# micro_mousev1_0.net
KiCad netlist of a schematic drawn in Altium Designer
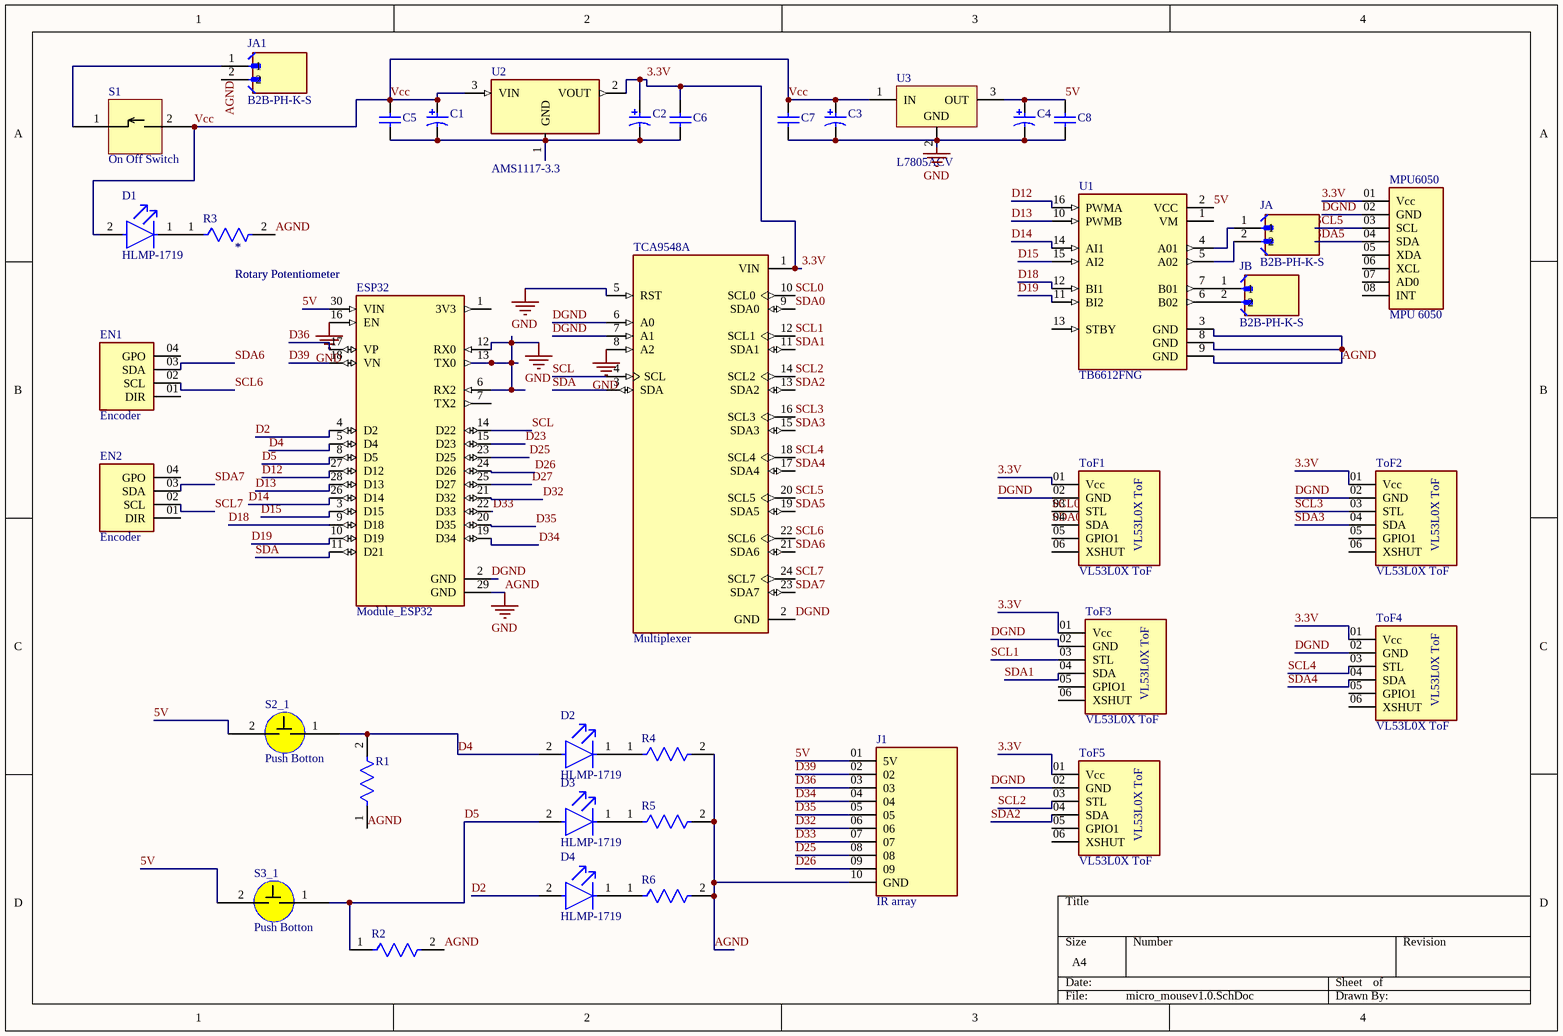
[diagram p0: micro_mousev1.0.SchDoc]

(export (version "E")
  (design (tool "Eeschema 10.0.6"))
  (components
    (comp (ref "C1")
      (value "ECA1HM100")
      (footprint "CAPPR55-200-1100X500X1200")
      (description "Aluminum Electrolytic Capacitor, 10 uF, +/- 20%, 50 V, -40 to 85 degC, 2-Pin THD, RoHS, Bulk")
      (fields (field (name "MANUFACTURER") "Panasonic") (field (name "TOLERANCE") "20%"))
      (libsource (lib "Altium Content Vault") (part "CAP-P-2"))
    )
    (comp (ref "C2")
      (value "ECA1HM100")
      (footprint "CAPPR55-200-1100X500X1200")
      (description "Aluminum Electrolytic Capacitor, 10 uF, +/- 20%, 50 V, -40 to 85 degC, 2-Pin THD, RoHS, Bulk")
      (fields (field (name "MANUFACTURER") "Panasonic") (field (name "TOLERANCE") "20%"))
      (libsource (lib "Altium Content Vault") (part "CAP-P-2"))
    )
    (comp (ref "C3")
      (value "ECA1HM100")
      (footprint "CAPPR55-200-1100X500X1200")
      (description "Aluminum Electrolytic Capacitor, 10 uF, +/- 20%, 50 V, -40 to 85 degC, 2-Pin THD, RoHS, Bulk")
      (fields (field (name "MANUFACTURER") "Panasonic") (field (name "TOLERANCE") "20%"))
      (libsource (lib "Altium Content Vault") (part "CAP-P-2"))
    )
    (comp (ref "C4")
      (value "ECA1HM100")
      (footprint "CAPPR55-200-1100X500X1200")
      (description "Aluminum Electrolytic Capacitor, 10 uF, +/- 20%, 50 V, -40 to 85 degC, 2-Pin THD, RoHS, Bulk")
      (fields (field (name "MANUFACTURER") "Panasonic") (field (name "TOLERANCE") "20%"))
      (libsource (lib "Altium Content Vault") (part "CAP-P-2"))
    )
    (comp (ref "C5")
      (value "K104K15X7RF5TL2")
      (footprint "VISH-K104K15X7RF5TL2")
      (description "Ceramic Capacitor, 100 nF, +/- 10%, 50 V, -55 to 125 degC, 2-Pin THD, RoHS, Tape and Reel")
      (fields (field (name "MANUFACTURER") "Vishay") (field (name "TOLERANCE") "±10%"))
      (libsource (lib "Altium Content Vault") (part "CAP-NP-2"))
    )
    (comp (ref "C6")
      (value "K104K15X7RF5TL2")
      (footprint "VISH-K104K15X7RF5TL2")
      (description "Ceramic Capacitor, 100 nF, +/- 10%, 50 V, -55 to 125 degC, 2-Pin THD, RoHS, Tape and Reel")
      (fields (field (name "MANUFACTURER") "Vishay") (field (name "TOLERANCE") "±10%"))
      (libsource (lib "Altium Content Vault") (part "CAP-NP-2"))
    )
    (comp (ref "C7")
      (value "K104K15X7RF5TL2")
      (footprint "VISH-K104K15X7RF5TL2")
      (description "Ceramic Capacitor, 100 nF, +/- 10%, 50 V, -55 to 125 degC, 2-Pin THD, RoHS, Tape and Reel")
      (fields (field (name "MANUFACTURER") "Vishay") (field (name "TOLERANCE") "±10%"))
      (libsource (lib "Altium Content Vault") (part "CAP-NP-2"))
    )
    (comp (ref "C8")
      (value "K104K15X7RF5TL2")
      (footprint "VISH-K104K15X7RF5TL2")
      (description "Ceramic Capacitor, 100 nF, +/- 10%, 50 V, -55 to 125 degC, 2-Pin THD, RoHS, Tape and Reel")
      (fields (field (name "MANUFACTURER") "Vishay") (field (name "TOLERANCE") "±10%"))
      (libsource (lib "Altium Content Vault") (part "CAP-NP-2"))
    )
    (comp (ref "D1")
      (value "HLMP-1719")
      (footprint "FP-HLMP-1719-MFG")
      (description "LED YELLOW DIFFUSED T-1 T/H")
      (fields
        (field (name "MANUFACTURER") "Broadcom")
        (field (name "OCTOPART") "https://octopart.com/hlmp-1719-broadcom-71130405")
      )
      (libsource (lib "Altium Content Vault") (part "8706943c75ba83719d021d2fdc84c58"))
    )
    (comp (ref "D2")
      (value "HLMP-1719")
      (footprint "FP-HLMP-1719-MFG")
      (description "LED YELLOW DIFFUSED T-1 T/H")
      (fields
        (field (name "MANUFACTURER") "Broadcom")
        (field (name "OCTOPART") "https://octopart.com/hlmp-1719-broadcom-71130405")
      )
      (libsource (lib "Altium Content Vault") (part "8706943c75ba83719d021d2fdc84c58"))
    )
    (comp (ref "D3")
      (value "HLMP-1719")
      (footprint "FP-HLMP-1719-MFG")
      (description "LED YELLOW DIFFUSED T-1 T/H")
      (fields
        (field (name "MANUFACTURER") "Broadcom")
        (field (name "OCTOPART") "https://octopart.com/hlmp-1719-broadcom-71130405")
      )
      (libsource (lib "Altium Content Vault") (part "8706943c75ba83719d021d2fdc84c58"))
    )
    (comp (ref "D4")
      (value "HLMP-1719")
      (footprint "FP-HLMP-1719-MFG")
      (description "LED YELLOW DIFFUSED T-1 T/H")
      (fields
        (field (name "MANUFACTURER") "Broadcom")
        (field (name "OCTOPART") "https://octopart.com/hlmp-1719-broadcom-71130405")
      )
      (libsource (lib "Altium Content Vault") (part "8706943c75ba83719d021d2fdc84c58"))
    )
    (comp (ref "EN1")
      (value "Encoder")
      (footprint "Encoder 4 pin")
      (description "Variable Post Height Header Strips, 2.00 mm Pitch")
      (fields (field (name "MF") "SAMTEC") (field (name "MP") "MTMM-104-08-T-S-315"))
      (libsource (lib "micro_mousev1.0") (part "Encoder"))
    )
    (comp (ref "EN2")
      (value "Encoder")
      (footprint "Encoder 4 pin")
      (description "Variable Post Height Header Strips, 2.00 mm Pitch")
      (fields (field (name "MF") "SAMTEC") (field (name "MP") "MTMM-104-08-T-S-315"))
      (libsource (lib "micro_mousev1.0") (part "Encoder"))
    )
    (comp (ref "ESP32")
      (value "Module_ESP32")
      (footprint "MODULE_ESP32_DEVKIT_V1")
      (libsource (lib "micro_mousev1.0") (part "Module_ESP32"))
    )
    (comp (ref "J1")
      (value "IR array")
      (footprint "IR array")
      (fields (field (name "MP") "TSW-210-15-L-S"))
      (libsource (lib "micro_mousev1.0") (part "IR array"))
    )
    (comp (ref "JA")
      (value "B2B-PH-K-S")
      (footprint "JST_B2B-PH-K-S")
      (description "Connector Header Through Hole 2 position 0.079 (2.00mm)")
      (fields (field (name "MF") "JST Sales America Inc."))
      (libsource (lib "micro_mousev1.0") (part "B2B-PH-K-S"))
    )
    (comp (ref "JA1")
      (value "B2B-PH-K-S")
      (footprint "JST_B2B-PH-K-S")
      (description "Connector Header Through Hole 2 position 0.079 (2.00mm)")
      (fields (field (name "MF") "JST Sales America Inc."))
      (libsource (lib "micro_mousev1.0") (part "B2B-PH-K-S"))
    )
    (comp (ref "JB")
      (value "B2B-PH-K-S")
      (footprint "JST_B2B-PH-K-S")
      (description "Connector Header Through Hole 2 position 0.079 (2.00mm)")
      (fields (field (name "MF") "JST Sales America Inc."))
      (libsource (lib "micro_mousev1.0") (part "B2B-PH-K-S"))
    )
    (comp (ref "MPU6050")
      (value "MPU 6050")
      (footprint "8 Pin MPU")
      (description "CONN HDR .050 8POS")
      (fields (field (name "MF") "Samtec") (field (name "MP") "MTMS-108-02-T-S-100"))
      (libsource (lib "micro_mousev1.0") (part "MPU 6050"))
    )
    (comp (ref "R1")
      (value "PCF14JT7K50")
      (footprint "FP-CF14-MFG")
      (description "RES 7.5K OHM 1/4W 5% AXIAL")
      (fields (field (name "TOLERANCE") "5%"))
      (libsource (lib "Altium Content Vault") (part "1029c3af85768c4190bb7ad29bc67b5"))
    )
    (comp (ref "R2")
      (value "PCF14JT7K50")
      (footprint "FP-CF14-MFG")
      (description "RES 7.5K OHM 1/4W 5% AXIAL")
      (fields (field (name "TOLERANCE") "5%"))
      (libsource (lib "Altium Content Vault") (part "1029c3af85768c4190bb7ad29bc67b5"))
    )
    (comp (ref "R3")
      (value "PCF14JT7K50")
      (footprint "FP-CF14-MFG")
      (description "RES 7.5K OHM 1/4W 5% AXIAL")
      (fields (field (name "TOLERANCE") "5%"))
      (libsource (lib "Altium Content Vault") (part "1029c3af85768c4190bb7ad29bc67b5"))
    )
    (comp (ref "R4")
      (value "PCF14JT7K50")
      (footprint "FP-CF14-MFG")
      (description "RES 7.5K OHM 1/4W 5% AXIAL")
      (fields (field (name "TOLERANCE") "5%"))
      (libsource (lib "Altium Content Vault") (part "1029c3af85768c4190bb7ad29bc67b5"))
    )
    (comp (ref "R5")
      (value "PCF14JT7K50")
      (footprint "FP-CF14-MFG")
      (description "RES 7.5K OHM 1/4W 5% AXIAL")
      (fields (field (name "TOLERANCE") "5%"))
      (libsource (lib "Altium Content Vault") (part "1029c3af85768c4190bb7ad29bc67b5"))
    )
    (comp (ref "R6")
      (value "PCF14JT7K50")
      (footprint "FP-CF14-MFG")
      (description "RES 7.5K OHM 1/4W 5% AXIAL")
      (fields (field (name "TOLERANCE") "5%"))
      (libsource (lib "Altium Content Vault") (part "1029c3af85768c4190bb7ad29bc67b5"))
    )
    (comp (ref "S1")
      (value "On Off Switch")
      (footprint "Switch")
      (libsource (lib "micro_mousev1.0") (part "On Off Switch"))
    )
    (comp (ref "S2_1")
      (value "Push Botton")
      (footprint "Push botton")
      (libsource (lib "micro_mousev1.0") (part "Push Botton"))
    )
    (comp (ref "S3_1")
      (value "Push Botton")
      (footprint "Push botton")
      (libsource (lib "micro_mousev1.0") (part "Push Botton"))
    )
    (comp (ref "TCA9548A")
      (value "Multiplexer")
      (footprint "MODULE_2717")
      (description "Module: multiplexer; I2C interface multiplexer; TCA9548A; 3Ã·5VDC")
      (fields (field (name "MF") "Adafruit") (field (name "MP") "2717"))
      (libsource (lib "micro_mousev1.0") (part "Multiplexer"))
    )
    (comp (ref "ToF1")
      (value "VL53L0X ToF")
      (footprint "VL53L0X ToF")
      (fields (field (name "MP") "ZW-06-09-L-S-312-160"))
      (libsource (lib "micro_mousev1.0") (part "VL53L0X ToF"))
    )
    (comp (ref "ToF2")
      (value "VL53L0X ToF")
      (footprint "VL53L0X ToF")
      (fields (field (name "MP") "ZW-06-09-L-S-312-160"))
      (libsource (lib "micro_mousev1.0") (part "VL53L0X ToF"))
    )
    (comp (ref "ToF3")
      (value "VL53L0X ToF")
      (footprint "VL53L0X ToF")
      (fields (field (name "MP") "ZW-06-09-L-S-312-160"))
      (libsource (lib "micro_mousev1.0") (part "VL53L0X ToF"))
    )
    (comp (ref "ToF4")
      (value "VL53L0X ToF")
      (footprint "VL53L0X ToF")
      (fields (field (name "MP") "ZW-06-09-L-S-312-160"))
      (libsource (lib "micro_mousev1.0") (part "VL53L0X ToF"))
    )
    (comp (ref "ToF5")
      (value "VL53L0X ToF")
      (footprint "VL53L0X ToF")
      (fields (field (name "MP") "ZW-06-09-L-S-312-160"))
      (libsource (lib "micro_mousev1.0") (part "VL53L0X ToF"))
    )
    (comp (ref "U1")
      (value "TB6612FNG")
      (footprint "TB6612FNG")
      (description "TB6612FNG Motor Controller/Driver Power Management Evaluation Board")
      (fields (field (name "MP") "ROB-14450") (field (name "MF") "SparkFun Electronics"))
      (libsource (lib "micro_mousev1.0") (part "TB6612FNG"))
    )
    (comp (ref "U2")
      (value "AMS1117-3.3")
      (footprint "SOT229P700X180-4N")
      (description "Sot223/Pkg 1-Amp 3.3-Volt Low Drop Out Voltage Regulatator")
      (fields (field (name "MF") "Advanced Monolithic Systems"))
      (libsource (lib "micro_mousev1.0") (part "AMS1117-3.3"))
    )
    (comp (ref "U3")
      (value "L7805ACV")
      (footprint "TO220")
      (description "Positive Voltage Regulator, 5V, 3-Pin TO-220")
      (libsource (lib "Altium Content Vault") (part "PM-REG-L4940-SIL3"))
    )
  )
  (nets
    (net (code "1") (name "/3.3V") (class "Default")
      (node (ref "C2") (pin "1") (pinfunction "1_1") (pintype "passive"))
      (node (ref "C6") (pin "2") (pinfunction "2_2") (pintype "passive"))
      (node (ref "MPU6050") (pin "01") (pinfunction "Vcc_01") (pintype "passive"))
      (node (ref "TCA9548A") (pin "1") (pinfunction "VIN_1") (pintype "power_in"))
      (node (ref "ToF1") (pin "01") (pinfunction "Vcc_01") (pintype "passive"))
      (node (ref "ToF2") (pin "01") (pinfunction "Vcc_01") (pintype "passive"))
      (node (ref "ToF3") (pin "01") (pinfunction "Vcc_01") (pintype "passive"))
      (node (ref "ToF4") (pin "01") (pinfunction "Vcc_01") (pintype "passive"))
      (node (ref "ToF5") (pin "01") (pinfunction "Vcc_01") (pintype "passive"))
      (node (ref "U2") (pin "2") (pinfunction "VOUT_2") (pintype "output"))
    )
    (net (code "2") (name "/5V") (class "Default")
      (node (ref "C4") (pin "1") (pinfunction "1_1") (pintype "passive"))
      (node (ref "C8") (pin "2") (pinfunction "2_2") (pintype "passive"))
      (node (ref "ESP32") (pin "30") (pinfunction "VIN_30") (pintype "input"))
      (node (ref "J1") (pin "01") (pinfunction "5V_01") (pintype "passive"))
      (node (ref "S2_1") (pin "2") (pinfunction "P29_2") (pintype "passive"))
      (node (ref "S3_1") (pin "2") (pinfunction "P29_2") (pintype "passive"))
      (node (ref "U1") (pin "2") (pinfunction "VCC_2") (pintype "power_in"))
      (node (ref "U3") (pin "3") (pinfunction "OUT_3") (pintype "power_in"))
    )
    (net (code "3") (name "/D2") (class "Default")
      (node (ref "D4") (pin "2") (pinfunction "A_2") (pintype "passive"))
      (node (ref "ESP32") (pin "4") (pinfunction "D2_4") (pintype "bidirectional"))
    )
    (net (code "4") (name "/D4") (class "Default")
      (node (ref "D2") (pin "2") (pinfunction "A_2") (pintype "passive"))
      (node (ref "ESP32") (pin "5") (pinfunction "D4_5") (pintype "bidirectional"))
      (node (ref "R1") (pin "2") (pinfunction "2_2") (pintype "passive"))
      (node (ref "S2_1") (pin "1") (pinfunction "P30_1") (pintype "passive"))
    )
    (net (code "5") (name "/D5") (class "Default")
      (node (ref "D3") (pin "2") (pinfunction "A_2") (pintype "passive"))
      (node (ref "ESP32") (pin "8") (pinfunction "D5_8") (pintype "bidirectional"))
      (node (ref "R2") (pin "1") (pinfunction "1_1") (pintype "passive"))
      (node (ref "S3_1") (pin "1") (pinfunction "P30_1") (pintype "passive"))
    )
    (net (code "6") (name "/D12") (class "Default")
      (node (ref "ESP32") (pin "27") (pinfunction "D12_27") (pintype "bidirectional"))
      (node (ref "U1") (pin "16") (pinfunction "PWMA_16") (pintype "input"))
    )
    (net (code "7") (name "/D13") (class "Default")
      (node (ref "ESP32") (pin "28") (pinfunction "D13_28") (pintype "bidirectional"))
      (node (ref "U1") (pin "10") (pinfunction "PWMB_10") (pintype "input"))
    )
    (net (code "8") (name "/D14") (class "Default")
      (node (ref "ESP32") (pin "26") (pinfunction "D14_26") (pintype "bidirectional"))
      (node (ref "U1") (pin "14") (pinfunction "AI1_14") (pintype "input"))
    )
    (net (code "9") (name "/D15") (class "Default")
      (node (ref "ESP32") (pin "3") (pinfunction "D15_3") (pintype "bidirectional"))
      (node (ref "U1") (pin "15") (pinfunction "AI2_15") (pintype "input"))
    )
    (net (code "10") (name "/D18") (class "Default")
      (node (ref "ESP32") (pin "9") (pinfunction "D18_9") (pintype "bidirectional"))
      (node (ref "U1") (pin "12") (pinfunction "BI1_12") (pintype "input"))
    )
    (net (code "11") (name "/D19") (class "Default")
      (node (ref "ESP32") (pin "10") (pinfunction "D19_10") (pintype "bidirectional"))
      (node (ref "U1") (pin "11") (pinfunction "BI2_11") (pintype "input"))
    )
    (net (code "12") (name "/D23") (class "Default")
      (node (ref "ESP32") (pin "15") (pinfunction "D23_15") (pintype "bidirectional"))
    )
    (net (code "13") (name "/D25") (class "Default")
      (node (ref "ESP32") (pin "23") (pinfunction "D25_23") (pintype "bidirectional"))
      (node (ref "J1") (pin "08") (pinfunction "08_08") (pintype "passive"))
    )
    (net (code "14") (name "/D26") (class "Default")
      (node (ref "ESP32") (pin "24") (pinfunction "D26_24") (pintype "bidirectional"))
      (node (ref "J1") (pin "09") (pinfunction "09_09") (pintype "passive"))
    )
    (net (code "15") (name "/D27") (class "Default")
      (node (ref "ESP32") (pin "25") (pinfunction "D27_25") (pintype "bidirectional"))
    )
    (net (code "16") (name "/D32") (class "Default")
      (node (ref "ESP32") (pin "21") (pinfunction "D32_21") (pintype "bidirectional"))
      (node (ref "J1") (pin "06") (pinfunction "06_06") (pintype "passive"))
    )
    (net (code "17") (name "/D33") (class "Default")
      (node (ref "ESP32") (pin "22") (pinfunction "D33_22") (pintype "bidirectional"))
      (node (ref "J1") (pin "07") (pinfunction "07_07") (pintype "passive"))
    )
    (net (code "18") (name "/D34") (class "Default")
      (node (ref "ESP32") (pin "19") (pinfunction "D34_19") (pintype "bidirectional"))
      (node (ref "J1") (pin "04") (pinfunction "04_04") (pintype "passive"))
    )
    (net (code "19") (name "/D35") (class "Default")
      (node (ref "ESP32") (pin "20") (pinfunction "D35_20") (pintype "bidirectional"))
      (node (ref "J1") (pin "05") (pinfunction "05_05") (pintype "passive"))
    )
    (net (code "20") (name "/D36") (class "Default")
      (node (ref "ESP32") (pin "17") (pinfunction "VP_17") (pintype "bidirectional"))
      (node (ref "J1") (pin "03") (pinfunction "03_03") (pintype "passive"))
    )
    (net (code "21") (name "/D39") (class "Default")
      (node (ref "ESP32") (pin "18") (pinfunction "VN_18") (pintype "bidirectional"))
      (node (ref "J1") (pin "02") (pinfunction "02_02") (pintype "passive"))
    )
    (net (code "22") (name "/DGND") (class "Default")
      (node (ref "ESP32") (pin "2") (pinfunction "GND_2") (pintype "power_in"))
      (node (ref "MPU6050") (pin "02") (pinfunction "GND_02") (pintype "passive"))
      (node (ref "TCA9548A") (pin "2") (pinfunction "GND_2") (pintype "power_in"))
      (node (ref "TCA9548A") (pin "6") (pinfunction "A0_6") (pintype "input"))
      (node (ref "TCA9548A") (pin "7") (pinfunction "A1_7") (pintype "input"))
      (node (ref "ToF1") (pin "02") (pinfunction "GND_02") (pintype "passive"))
      (node (ref "ToF2") (pin "02") (pinfunction "GND_02") (pintype "passive"))
      (node (ref "ToF3") (pin "02") (pinfunction "GND_02") (pintype "passive"))
      (node (ref "ToF4") (pin "02") (pinfunction "GND_02") (pintype "passive"))
      (node (ref "ToF5") (pin "02") (pinfunction "GND_02") (pintype "passive"))
    )
    (net (code "23") (name "/SCL") (class "Default")
      (node (ref "ESP32") (pin "14") (pinfunction "D22_14") (pintype "bidirectional"))
      (node (ref "TCA9548A") (pin "4") (pinfunction "SCL_4") (pintype "input"))
    )
    (net (code "24") (name "/SCL0") (class "Default")
      (node (ref "TCA9548A") (pin "10") (pinfunction "SCL0_10") (pintype "output"))
      (node (ref "ToF1") (pin "03") (pinfunction "STL_03") (pintype "passive"))
    )
    (net (code "25") (name "/SCL1") (class "Default")
      (node (ref "TCA9548A") (pin "12") (pinfunction "SCL1_12") (pintype "output"))
      (node (ref "ToF3") (pin "03") (pinfunction "STL_03") (pintype "passive"))
    )
    (net (code "26") (name "/SCL2") (class "Default")
      (node (ref "TCA9548A") (pin "14") (pinfunction "SCL2_14") (pintype "output"))
      (node (ref "ToF5") (pin "03") (pinfunction "STL_03") (pintype "passive"))
    )
    (net (code "27") (name "/SCL3") (class "Default")
      (node (ref "TCA9548A") (pin "16") (pinfunction "SCL3_16") (pintype "output"))
      (node (ref "ToF2") (pin "03") (pinfunction "STL_03") (pintype "passive"))
    )
    (net (code "28") (name "/SCL4") (class "Default")
      (node (ref "TCA9548A") (pin "18") (pinfunction "SCL4_18") (pintype "output"))
      (node (ref "ToF4") (pin "03") (pinfunction "STL_03") (pintype "passive"))
    )
    (net (code "29") (name "/SCL5") (class "Default")
      (node (ref "MPU6050") (pin "03") (pinfunction "SCL_03") (pintype "passive"))
      (node (ref "TCA9548A") (pin "20") (pinfunction "SCL5_20") (pintype "output"))
    )
    (net (code "30") (name "/SCL6") (class "Default")
      (node (ref "EN1") (pin "02") (pinfunction "SCL_02") (pintype "passive"))
      (node (ref "TCA9548A") (pin "22") (pinfunction "SCL6_22") (pintype "output"))
    )
    (net (code "31") (name "/SCL7") (class "Default")
      (node (ref "EN2") (pin "02") (pinfunction "SCL_02") (pintype "passive"))
      (node (ref "TCA9548A") (pin "24") (pinfunction "SCL7_24") (pintype "output"))
    )
    (net (code "32") (name "/SDA") (class "Default")
      (node (ref "ESP32") (pin "11") (pinfunction "D21_11") (pintype "bidirectional"))
      (node (ref "TCA9548A") (pin "3") (pinfunction "SDA_3") (pintype "bidirectional"))
    )
    (net (code "33") (name "/SDA0") (class "Default")
      (node (ref "TCA9548A") (pin "9") (pinfunction "SDA0_9") (pintype "bidirectional"))
      (node (ref "ToF1") (pin "04") (pinfunction "SDA_04") (pintype "passive"))
    )
    (net (code "34") (name "/SDA1") (class "Default")
      (node (ref "TCA9548A") (pin "11") (pinfunction "SDA1_11") (pintype "bidirectional"))
      (node (ref "ToF3") (pin "04") (pinfunction "SDA_04") (pintype "passive"))
    )
    (net (code "35") (name "/SDA2") (class "Default")
      (node (ref "TCA9548A") (pin "13") (pinfunction "SDA2_13") (pintype "bidirectional"))
      (node (ref "ToF5") (pin "04") (pinfunction "SDA_04") (pintype "passive"))
    )
    (net (code "36") (name "/SDA3") (class "Default")
      (node (ref "TCA9548A") (pin "15") (pinfunction "SDA3_15") (pintype "bidirectional"))
      (node (ref "ToF2") (pin "04") (pinfunction "SDA_04") (pintype "passive"))
    )
    (net (code "37") (name "/SDA4") (class "Default")
      (node (ref "TCA9548A") (pin "17") (pinfunction "SDA4_17") (pintype "bidirectional"))
      (node (ref "ToF4") (pin "04") (pinfunction "SDA_04") (pintype "passive"))
    )
    (net (code "38") (name "/SDA5") (class "Default")
      (node (ref "MPU6050") (pin "04") (pinfunction "SDA_04") (pintype "passive"))
      (node (ref "TCA9548A") (pin "19") (pinfunction "SDA5_19") (pintype "bidirectional"))
    )
    (net (code "39") (name "/SDA6") (class "Default")
      (node (ref "EN1") (pin "03") (pinfunction "SDA_03") (pintype "passive"))
      (node (ref "TCA9548A") (pin "21") (pinfunction "SDA6_21") (pintype "bidirectional"))
    )
    (net (code "40") (name "/SDA7") (class "Default")
      (node (ref "EN2") (pin "03") (pinfunction "SDA_03") (pintype "passive"))
      (node (ref "TCA9548A") (pin "23") (pinfunction "SDA7_23") (pintype "bidirectional"))
    )
    (net (code "41") (name "/Vcc") (class "Default")
      (node (ref "C1") (pin "1") (pinfunction "1_1") (pintype "passive"))
      (node (ref "C3") (pin "1") (pinfunction "1_1") (pintype "passive"))
      (node (ref "C5") (pin "2") (pinfunction "2_2") (pintype "passive"))
      (node (ref "C7") (pin "2") (pinfunction "2_2") (pintype "passive"))
      (node (ref "D1") (pin "2") (pinfunction "A_2") (pintype "passive"))
      (node (ref "S1") (pin "2") (pintype "passive"))
      (node (ref "U2") (pin "3") (pinfunction "VIN_3") (pintype "input"))
      (node (ref "U3") (pin "1") (pinfunction "IN_1") (pintype "power_in"))
    )
    (net (code "42") (name "GND") (class "Default")
      (node (ref "C3") (pin "2") (pinfunction "2_2") (pintype "passive"))
      (node (ref "C4") (pin "2") (pinfunction "2_2") (pintype "passive"))
      (node (ref "C7") (pin "1") (pinfunction "1_1") (pintype "passive"))
      (node (ref "C8") (pin "1") (pinfunction "1_1") (pintype "passive"))
      (node (ref "ESP32") (pin "12") (pinfunction "RX0_12") (pintype "input"))
      (node (ref "ESP32") (pin "13") (pinfunction "TX0_13") (pintype "output"))
      (node (ref "ESP32") (pin "16") (pinfunction "EN_16") (pintype "input"))
      (node (ref "ESP32") (pin "29") (pinfunction "GND_29") (pintype "power_in"))
      (node (ref "ESP32") (pin "6") (pinfunction "RX2_6") (pintype "input"))
      (node (ref "J1") (pin "10") (pinfunction "GND_10") (pintype "passive"))
      (node (ref "JA1") (pin "2") (pinfunction "2_2") (pintype "passive"))
      (node (ref "R1") (pin "1") (pinfunction "1_1") (pintype "passive"))
      (node (ref "R2") (pin "2") (pinfunction "2_2") (pintype "passive"))
      (node (ref "R3") (pin "2") (pinfunction "2_2") (pintype "passive"))
      (node (ref "R4") (pin "2") (pinfunction "2_2") (pintype "passive"))
      (node (ref "R5") (pin "2") (pinfunction "2_2") (pintype "passive"))
      (node (ref "R6") (pin "2") (pinfunction "2_2") (pintype "passive"))
      (node (ref "TCA9548A") (pin "5") (pinfunction "RST_5") (pintype "input"))
      (node (ref "TCA9548A") (pin "8") (pinfunction "A2_8") (pintype "input"))
      (node (ref "U1") (pin "3") (pinfunction "GND_3") (pintype "power_in"))
      (node (ref "U1") (pin "8") (pinfunction "GND_8") (pintype "power_in"))
      (node (ref "U1") (pin "9") (pinfunction "GND_9") (pintype "power_in"))
    )
    (net (code "43") (name "Net-(D1-C)") (class "Default")
      (node (ref "D1") (pin "1") (pinfunction "C_1") (pintype "passive"))
      (node (ref "R3") (pin "1") (pinfunction "1_1") (pintype "passive"))
    )
    (net (code "44") (name "Net-(D2-C)") (class "Default")
      (node (ref "D2") (pin "1") (pinfunction "C_1") (pintype "passive"))
      (node (ref "R4") (pin "1") (pinfunction "1_1") (pintype "passive"))
    )
    (net (code "45") (name "Net-(D3-C)") (class "Default")
      (node (ref "D3") (pin "1") (pinfunction "C_1") (pintype "passive"))
      (node (ref "R5") (pin "1") (pinfunction "1_1") (pintype "passive"))
    )
    (net (code "46") (name "Net-(D4-C)") (class "Default")
      (node (ref "D4") (pin "1") (pinfunction "C_1") (pintype "passive"))
      (node (ref "R6") (pin "1") (pinfunction "1_1") (pintype "passive"))
    )
    (net (code "47") (name "Net-(S1-P27)") (class "Default")
      (node (ref "JA1") (pin "1") (pinfunction "1_1") (pintype "passive"))
      (node (ref "S1") (pin "1") (pinfunction "P27_1") (pintype "passive"))
    )
    (net (code "48") (name "Net-(U1-A01)") (class "Default")
      (node (ref "JA") (pin "1") (pinfunction "1_1") (pintype "passive"))
      (node (ref "U1") (pin "4") (pinfunction "A01_4") (pintype "output"))
    )
    (net (code "49") (name "Net-(U1-A02)") (class "Default")
      (node (ref "JA") (pin "2") (pinfunction "2_2") (pintype "passive"))
      (node (ref "U1") (pin "5") (pinfunction "A02_5") (pintype "output"))
    )
    (net (code "50") (name "Net-(U1-B01)") (class "Default")
      (node (ref "JB") (pin "1") (pinfunction "1_1") (pintype "passive"))
      (node (ref "U1") (pin "7") (pinfunction "B01_7") (pintype "output"))
    )
    (net (code "51") (name "Net-(U1-B02)") (class "Default")
      (node (ref "JB") (pin "2") (pinfunction "2_2") (pintype "passive"))
      (node (ref "U1") (pin "6") (pinfunction "B02_6") (pintype "output"))
    )
    (net (code "52") (name "Net-(U2-GND)") (class "Default")
      (node (ref "C1") (pin "2") (pinfunction "2_2") (pintype "passive"))
      (node (ref "C2") (pin "2") (pinfunction "2_2") (pintype "passive"))
      (node (ref "C5") (pin "1") (pinfunction "1_1") (pintype "passive"))
      (node (ref "C6") (pin "1") (pinfunction "1_1") (pintype "passive"))
      (node (ref "U2") (pin "1") (pinfunction "GND_1") (pintype "power_in"))
    )
    (net (code "53") (name "unconnected-(EN1-DIR-Pad01)") (class "Default")
      (node (ref "EN1") (pin "01") (pinfunction "DIR_01") (pintype "passive"))
    )
    (net (code "54") (name "unconnected-(EN1-GPO-Pad04)") (class "Default")
      (node (ref "EN1") (pin "04") (pinfunction "GPO_04") (pintype "passive"))
    )
    (net (code "55") (name "unconnected-(EN2-DIR-Pad01)") (class "Default")
      (node (ref "EN2") (pin "01") (pinfunction "DIR_01") (pintype "passive"))
    )
    (net (code "56") (name "unconnected-(EN2-GPO-Pad04)") (class "Default")
      (node (ref "EN2") (pin "04") (pinfunction "GPO_04") (pintype "passive"))
    )
    (net (code "57") (name "unconnected-(ESP32-3V3-Pad1)") (class "Default")
      (node (ref "ESP32") (pin "1") (pinfunction "3V3_1") (pintype "output"))
    )
    (net (code "58") (name "unconnected-(ESP32-TX2-Pad7)") (class "Default")
      (node (ref "ESP32") (pin "7") (pinfunction "TX2_7") (pintype "output"))
    )
    (net (code "59") (name "unconnected-(MPU6050-AD0-Pad07)") (class "Default")
      (node (ref "MPU6050") (pin "07") (pinfunction "AD0_07") (pintype "passive"))
    )
    (net (code "60") (name "unconnected-(MPU6050-INT-Pad08)") (class "Default")
      (node (ref "MPU6050") (pin "08") (pinfunction "INT_08") (pintype "passive"))
    )
    (net (code "61") (name "unconnected-(MPU6050-XCL-Pad06)") (class "Default")
      (node (ref "MPU6050") (pin "06") (pinfunction "XCL_06") (pintype "passive"))
    )
    (net (code "62") (name "unconnected-(MPU6050-XDA-Pad05)") (class "Default")
      (node (ref "MPU6050") (pin "05") (pinfunction "XDA_05") (pintype "passive"))
    )
    (net (code "63") (name "unconnected-(ToF1-GPIO1-Pad05)") (class "Default")
      (node (ref "ToF1") (pin "05") (pinfunction "GPIO1_05") (pintype "passive"))
    )
    (net (code "64") (name "unconnected-(ToF1-XSHUT-Pad06)") (class "Default")
      (node (ref "ToF1") (pin "06") (pinfunction "XSHUT_06") (pintype "passive"))
    )
    (net (code "65") (name "unconnected-(ToF2-GPIO1-Pad05)") (class "Default")
      (node (ref "ToF2") (pin "05") (pinfunction "GPIO1_05") (pintype "passive"))
    )
    (net (code "66") (name "unconnected-(ToF2-XSHUT-Pad06)") (class "Default")
      (node (ref "ToF2") (pin "06") (pinfunction "XSHUT_06") (pintype "passive"))
    )
    (net (code "67") (name "unconnected-(ToF3-GPIO1-Pad05)") (class "Default")
      (node (ref "ToF3") (pin "05") (pinfunction "GPIO1_05") (pintype "passive"))
    )
    (net (code "68") (name "unconnected-(ToF3-XSHUT-Pad06)") (class "Default")
      (node (ref "ToF3") (pin "06") (pinfunction "XSHUT_06") (pintype "passive"))
    )
    (net (code "69") (name "unconnected-(ToF4-GPIO1-Pad05)") (class "Default")
      (node (ref "ToF4") (pin "05") (pinfunction "GPIO1_05") (pintype "passive"))
    )
    (net (code "70") (name "unconnected-(ToF4-XSHUT-Pad06)") (class "Default")
      (node (ref "ToF4") (pin "06") (pinfunction "XSHUT_06") (pintype "passive"))
    )
    (net (code "71") (name "unconnected-(ToF5-GPIO1-Pad05)") (class "Default")
      (node (ref "ToF5") (pin "05") (pinfunction "GPIO1_05") (pintype "passive"))
    )
    (net (code "72") (name "unconnected-(ToF5-XSHUT-Pad06)") (class "Default")
      (node (ref "ToF5") (pin "06") (pinfunction "XSHUT_06") (pintype "passive"))
    )
    (net (code "73") (name "unconnected-(U1-STBY-Pad13)") (class "Default")
      (node (ref "U1") (pin "13") (pinfunction "STBY_13") (pintype "input"))
    )
    (net (code "74") (name "unconnected-(U1-VM-Pad1)") (class "Default")
      (node (ref "U1") (pin "1") (pinfunction "VM_1") (pintype "power_in"))
    )
    (net (code "75") (name "unconnected-(U3-GND-Pad2)") (class "Default")
      (node (ref "U3") (pin "2") (pinfunction "GND_2") (pintype "power_in"))
    )
  )
)
